# 13_TYPEC0_PROG.net
KiCad netlist of a schematic drawn in Altium Designer
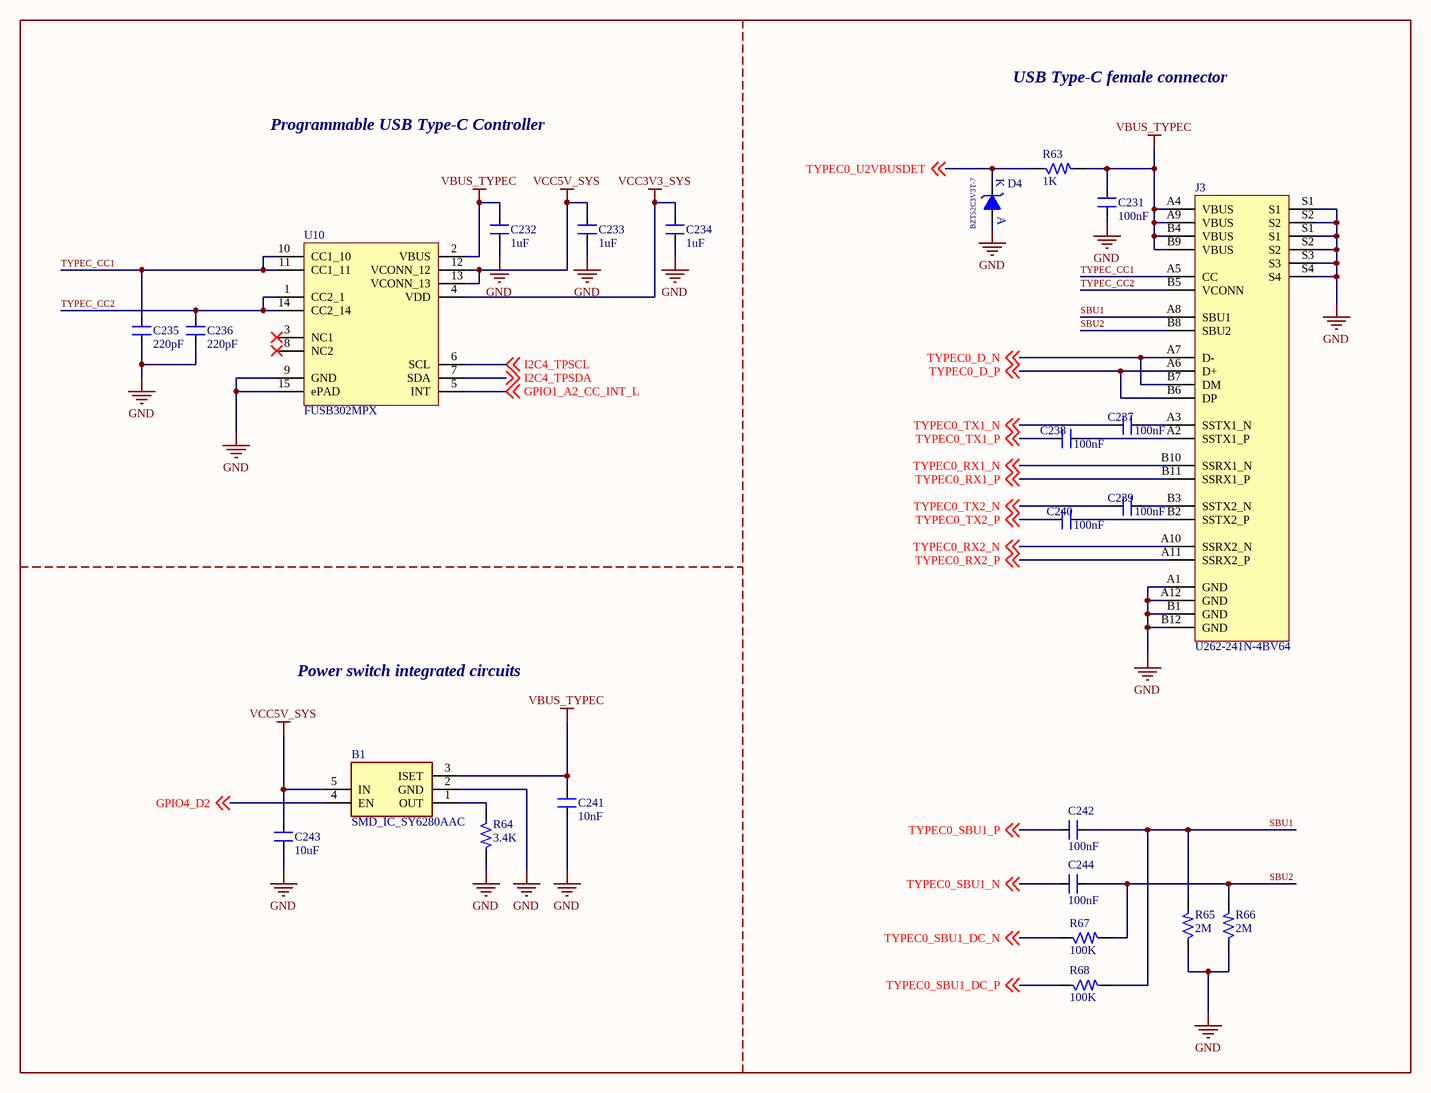
[diagram p0: [13] TYPEC0_PROG.SchDoc]

(export (version "E")
  (design (tool "Eeschema 10.0.6"))
  (components
    (comp (ref "B1")
      (value "SMD_IC_SY6280AAC")
      (footprint "SOT95P285X140-5N")
      (description "Power Switch ICs - Power Distribution")
      (fields
        (field (name "MOUSER PART NUMBER") "909-SMDICSY6280AAC")
        (field (name "MANUFACTURER_PART_NUMBER") "SMD IC SY6280AAC")
      )
      (libsource (lib "SMD_IC_SY6280AAC") (part "SMD_IC_SY6280AAC"))
    )
    (comp (ref "C231")
      (value "100nF")
      (footprint "CAP_0402")
      (description "0.1µF ±10% 25V Ceramic Capacitor X7R 0402 (1005 Metric)")
      (fields
        (field (name "MANUFACTURER") "Walsin Technology Corporation")
        (field (name "MANUFACTURER PART NUMBER") "0402B104K250CT")
      )
      (libsource (lib "EsteemPCB_SOM_Course_intlib") (part "CAP_100nF-25V-10%-0402"))
    )
    (comp (ref "C232")
      (value "1uF")
      (footprint "CAP_0402")
      (description "1µF ±10% 10V Ceramic Capacitor X6S 0402 (1005 Metric)")
      (fields
        (field (name "MANUFACTURER") "Murata Electronics")
        (field (name "MANUFACTURER PART NUMBER") "GRT155C81A105KE01D")
      )
      (libsource (lib "EsteemPCB_SOM_Course_intlib") (part "CAP_1uF-10V-10%-0402"))
    )
    (comp (ref "C233")
      (value "1uF")
      (footprint "CAP_0402")
      (description "1µF ±10% 10V Ceramic Capacitor X6S 0402 (1005 Metric)")
      (fields
        (field (name "MANUFACTURER") "Murata Electronics")
        (field (name "MANUFACTURER PART NUMBER") "GRT155C81A105KE01D")
      )
      (libsource (lib "EsteemPCB_SOM_Course_intlib") (part "CAP_1uF-10V-10%-0402"))
    )
    (comp (ref "C234")
      (value "1uF")
      (footprint "CAP_0402")
      (description "1µF ±10% 10V Ceramic Capacitor X6S 0402 (1005 Metric)")
      (fields
        (field (name "MANUFACTURER") "Murata Electronics")
        (field (name "MANUFACTURER PART NUMBER") "GRT155C81A105KE01D")
      )
      (libsource (lib "EsteemPCB_SOM_Course_intlib") (part "CAP_1uF-10V-10%-0402"))
    )
    (comp (ref "C235")
      (value "220pF")
      (footprint "CAP_0402")
      (description "220pF ±10% 10V Ceramic Capacitor X7R 0402 (1005 Metric)")
      (fields
        (field (name "MANUFACTURER") "KEMET")
        (field (name "MANUFACTURER PART NUMBER") "C0402C221K8RAC7867")
      )
      (libsource (lib "EsteemPCB_SOM_Course_intlib") (part "CAP_220pF-10V-10%-0402"))
    )
    (comp (ref "C236")
      (value "220pF")
      (footprint "CAP_0402")
      (description "220pF ±10% 10V Ceramic Capacitor X7R 0402 (1005 Metric)")
      (fields
        (field (name "MANUFACTURER") "KEMET")
        (field (name "MANUFACTURER PART NUMBER") "C0402C221K8RAC7867")
      )
      (libsource (lib "EsteemPCB_SOM_Course_intlib") (part "CAP_220pF-10V-10%-0402"))
    )
    (comp (ref "C237")
      (value "100nF")
      (footprint "CAP_0201")
      (description "0.1µF ±10% 25V Ceramic Capacitor X5R 0201 (0603 Metric)")
      (fields
        (field (name "MANUFACTURER") "TDK Corporation")
        (field (name "MANUFACTURER PART NUMBER") "C0603X5R1E104K030BB")
      )
      (libsource (lib "EsteemPCB_SOM_Course_intlib") (part "CAP_100nF-25V-10%-0201"))
    )
    (comp (ref "C238")
      (value "100nF")
      (footprint "CAP_0201")
      (description "0.1µF ±10% 25V Ceramic Capacitor X5R 0201 (0603 Metric)")
      (fields
        (field (name "MANUFACTURER") "TDK Corporation")
        (field (name "MANUFACTURER PART NUMBER") "C0603X5R1E104K030BB")
      )
      (libsource (lib "EsteemPCB_SOM_Course_intlib") (part "CAP_100nF-25V-10%-0201"))
    )
    (comp (ref "C239")
      (value "100nF")
      (footprint "CAP_0201")
      (description "0.1µF ±10% 25V Ceramic Capacitor X5R 0201 (0603 Metric)")
      (fields
        (field (name "MANUFACTURER") "TDK Corporation")
        (field (name "MANUFACTURER PART NUMBER") "C0603X5R1E104K030BB")
      )
      (libsource (lib "EsteemPCB_SOM_Course_intlib") (part "CAP_100nF-25V-10%-0201"))
    )
    (comp (ref "C240")
      (value "100nF")
      (footprint "CAP_0201")
      (description "0.1µF ±10% 25V Ceramic Capacitor X5R 0201 (0603 Metric)")
      (fields
        (field (name "MANUFACTURER") "TDK Corporation")
        (field (name "MANUFACTURER PART NUMBER") "C0603X5R1E104K030BB")
      )
      (libsource (lib "EsteemPCB_SOM_Course_intlib") (part "CAP_100nF-25V-10%-0201"))
    )
    (comp (ref "C241")
      (value "10nF")
      (footprint "CAP_0402")
      (description "10000pF ±10% 10V Ceramic Capacitor X7R 0402 (1005 Metric)")
      (fields
        (field (name "MANUFACTURER") "AVX Corporation")
        (field (name "MANUFACTURER PART NUMBER") "0402ZC103KAT2A")
      )
      (libsource (lib "EsteemPCB_SOM_Course_intlib") (part "CAP_10nF-10V-10%-0402"))
    )
    (comp (ref "C242")
      (value "100nF")
      (footprint "CAP_0201")
      (description "0.1µF ±10% 25V Ceramic Capacitor X5R 0201 (0603 Metric)")
      (fields
        (field (name "MANUFACTURER") "TDK Corporation")
        (field (name "MANUFACTURER PART NUMBER") "C0603X5R1E104K030BB")
      )
      (libsource (lib "EsteemPCB_SOM_Course_intlib") (part "CAP_100nF-25V-10%-0201"))
    )
    (comp (ref "C243")
      (value "10uF")
      (footprint "CAP_0402")
      (description "10µF ±20% 10V Ceramic Capacitor X5R 0402 (1005 Metric)")
      (fields
        (field (name "MANUFACTURER PART NUMBER") "CL05A106MP5NUNC")
        (field (name "MANUFACTURER") "Samsung Electro-Mechanics")
      )
      (libsource (lib "EsteemPCB_SOM_Course_intlib") (part "CAP_10uF-10V-20%-0402"))
    )
    (comp (ref "C244")
      (value "100nF")
      (footprint "CAP_0201")
      (description "0.1µF ±10% 25V Ceramic Capacitor X5R 0201 (0603 Metric)")
      (fields
        (field (name "MANUFACTURER") "TDK Corporation")
        (field (name "MANUFACTURER PART NUMBER") "C0603X5R1E104K030BB")
      )
      (libsource (lib "EsteemPCB_SOM_Course_intlib") (part "CAP_100nF-25V-10%-0201"))
    )
    (comp (ref "D4")
      (value "BZT52C3V3T-7")
      (footprint "DIO_SOD523")
      (description "Zener Diode 3.3V 300mW ±6% Surface Mount SOD-523")
      (fields (field (name "MANUFACTURER") "Diodes Incorporated"))
      (libsource (lib "EsteemPCB_SOM_Course_intlib") (part "DIO-Z_3.3V-300mW-SOD-523"))
    )
    (comp (ref "J3")
      (value "U262-241N-4BV64")
      (footprint "CON24_19.64_U262-241N-4BV64_TH_RA")
      (description "USB - Type C Female 24 SMD USB Connectors RoHS")
      (fields (field (name "MANUFACTURER") "XKB Connectivity"))
      (libsource (lib "EsteemPCB_SOM_Course_intlib") (part "CON-TYPEC_U262-241N-4BV64-SMD"))
    )
    (comp (ref "R63")
      (value "1K")
      (footprint "RES_0402")
      (description "1 kOhms ±1% 0.1W, 1/10W Chip Resistor 0402 (1005 Metric) Anti-Sulfur Thin Film")
      (fields
        (field (name "MANUFACTURER") "Vishay Beyschlag/Draloric/BC Components")
        (field (name "MANUFACTURER PART NUMBER") "MCS04020C1001FE000")
      )
      (libsource (lib "EsteemPCB_SOM_Course_intlib") (part "RES_1K-0.1W-1%-0402"))
    )
    (comp (ref "R64")
      (value "3.4K")
      (footprint "RES_0402")
      (description "3.4 kOhms ±1% 0.1W, 1/10W Chip Resistor 0402 (1005 Metric) Automotive AEC-Q200 Thick Film")
      (fields
        (field (name "MANUFACTURER") "Panasonic Electronic Components")
        (field (name "MANUFACTURER PART NUMBER") "ERJ-2RKF3401X")
      )
      (libsource (lib "EsteemPCB_SOM_Course_intlib") (part "RES_3.4K-0.1W-1%-0402"))
    )
    (comp (ref "R65")
      (value "2M")
      (footprint "RES_0201")
      (description "2 MOhms ±1% 0.05W, 1/20W Chip Resistor 0201 (0603 Metric) Thick Film")
      (fields
        (field (name "MANUFACTURER") "Yageo")
        (field (name "MANUFACTURER PART NUMBER") "RC0201FR-072ML")
      )
      (libsource (lib "EsteemPCB_SOM_Course_intlib") (part "RES_2M-0.05W-1%-0201"))
    )
    (comp (ref "R66")
      (value "2M")
      (footprint "RES_0201")
      (description "2 MOhms ±1% 0.05W, 1/20W Chip Resistor 0201 (0603 Metric) Thick Film")
      (fields
        (field (name "MANUFACTURER") "Yageo")
        (field (name "MANUFACTURER PART NUMBER") "RC0201FR-072ML")
      )
      (libsource (lib "EsteemPCB_SOM_Course_intlib") (part "RES_2M-0.05W-1%-0201"))
    )
    (comp (ref "R67")
      (value "100K")
      (footprint "RES_0201")
      (description "100 kOhms ±1% 0.05W, 1/20W Chip Resistor 0201 (0603 Metric) Automotive AEC-Q200 Thick Film")
      (fields
        (field (name "MANUFACTURER") "Panasonic Electronic Components")
        (field (name "MANUFACTURER PART NUMBER") "ERJ-1GNF1003C")
      )
      (libsource (lib "EsteemPCB_SOM_Course_intlib") (part "RES_100K-0.05W-1%-0201"))
    )
    (comp (ref "R68")
      (value "100K")
      (footprint "RES_0201")
      (description "100 kOhms ±1% 0.05W, 1/20W Chip Resistor 0201 (0603 Metric) Automotive AEC-Q200 Thick Film")
      (fields
        (field (name "MANUFACTURER") "Panasonic Electronic Components")
        (field (name "MANUFACTURER PART NUMBER") "ERJ-1GNF1003C")
      )
      (libsource (lib "EsteemPCB_SOM_Course_intlib") (part "RES_100K-0.05W-1%-0201"))
    )
    (comp (ref "U10")
      (value "FUSB302MPX")
      (footprint "MLP-14_98.4X98.4_SMD")
      (description "USB Controller USB 3.1 USB Interface 14-MLP (2.5x2.5)")
      (fields (field (name "MANUFACTURER") "ON Semiconductor"))
      (libsource (lib "EsteemPCB_SOM_Course_intlib") (part "IC_FUSB302MPX"))
    )
  )
  (nets
    (net (code "1") (name "/SBU1") (class "Default")
      (node (ref "C242") (pin "2") (pinfunction "2_2") (pintype "passive"))
      (node (ref "J3") (pin "A8") (pinfunction "SBU1_A8") (pintype "passive"))
      (node (ref "R65") (pin "2") (pinfunction "2_2") (pintype "passive"))
      (node (ref "R68") (pin "2") (pinfunction "2_2") (pintype "passive"))
    )
    (net (code "2") (name "/SBU2") (class "Default")
      (node (ref "C244") (pin "2") (pinfunction "2_2") (pintype "passive"))
      (node (ref "J3") (pin "B8") (pinfunction "SBU2_B8") (pintype "passive"))
      (node (ref "R66") (pin "2") (pinfunction "2_2") (pintype "passive"))
      (node (ref "R67") (pin "2") (pinfunction "2_2") (pintype "passive"))
    )
    (net (code "3") (name "/TYPEC_CC1") (class "Default")
      (node (ref "C235") (pin "2") (pinfunction "2_2") (pintype "passive"))
      (node (ref "J3") (pin "A5") (pinfunction "CC_A5") (pintype "passive"))
      (node (ref "U10") (pin "10") (pinfunction "CC1_10_10") (pintype "passive"))
      (node (ref "U10") (pin "11") (pinfunction "CC1_11_11") (pintype "passive"))
    )
    (net (code "4") (name "/TYPEC_CC2") (class "Default")
      (node (ref "C236") (pin "2") (pinfunction "2_2") (pintype "passive"))
      (node (ref "J3") (pin "B5") (pinfunction "VCONN_B5") (pintype "passive"))
      (node (ref "U10") (pin "1") (pinfunction "CC2_1_1") (pintype "passive"))
      (node (ref "U10") (pin "14") (pinfunction "CC2_14_14") (pintype "passive"))
    )
    (net (code "5") (name "GND") (class "Default")
      (node (ref "B1") (pin "2") (pinfunction "GND_2") (pintype "passive"))
      (node (ref "C231") (pin "1") (pinfunction "1_1") (pintype "passive"))
      (node (ref "C232") (pin "1") (pinfunction "1_1") (pintype "passive"))
      (node (ref "C233") (pin "2") (pinfunction "2_2") (pintype "passive"))
      (node (ref "C234") (pin "1") (pinfunction "1_1") (pintype "passive"))
      (node (ref "C235") (pin "1") (pinfunction "1_1") (pintype "passive"))
      (node (ref "C236") (pin "1") (pinfunction "1_1") (pintype "passive"))
      (node (ref "C241") (pin "1") (pinfunction "1_1") (pintype "passive"))
      (node (ref "C243") (pin "1") (pinfunction "1_1") (pintype "passive"))
      (node (ref "D4") (pin "A") (pinfunction "A_A") (pintype "passive"))
      (node (ref "J3") (pin "A1") (pinfunction "GND_A1") (pintype "passive"))
      (node (ref "J3") (pin "A12") (pinfunction "GND_A12") (pintype "passive"))
      (node (ref "J3") (pin "B1") (pinfunction "GND_B1") (pintype "passive"))
      (node (ref "J3") (pin "B12") (pinfunction "GND_B12") (pintype "passive"))
      (node (ref "J3") (pin "S1") (pinfunction "S1_S1") (pintype "passive"))
      (node (ref "J3") (pin "S2") (pinfunction "S2_S2") (pintype "passive"))
      (node (ref "J3") (pin "S3") (pinfunction "S3_S3") (pintype "passive"))
      (node (ref "J3") (pin "S4") (pinfunction "S4_S4") (pintype "passive"))
      (node (ref "R64") (pin "2") (pinfunction "2_2") (pintype "passive"))
      (node (ref "R65") (pin "1") (pinfunction "1_1") (pintype "passive"))
      (node (ref "R66") (pin "1") (pinfunction "1_1") (pintype "passive"))
      (node (ref "U10") (pin "15") (pinfunction "ePAD_15") (pintype "passive"))
      (node (ref "U10") (pin "9") (pinfunction "GND_9") (pintype "passive"))
    )
    (net (code "6") (name "GPIO1_A2_CC_INT_L") (class "Default")
      (node (ref "U10") (pin "5") (pinfunction "INT_5") (pintype "passive"))
    )
    (net (code "7") (name "GPIO4_D2") (class "Default")
      (node (ref "B1") (pin "4") (pinfunction "EN_4") (pintype "passive"))
    )
    (net (code "8") (name "I2C4_TPSCL") (class "Default")
      (node (ref "U10") (pin "6") (pinfunction "SCL_6") (pintype "passive"))
    )
    (net (code "9") (name "I2C4_TPSDA") (class "Default")
      (node (ref "U10") (pin "7") (pinfunction "SDA_7") (pintype "passive"))
    )
    (net (code "10") (name "Net-(B1-OUT)") (class "Default")
      (node (ref "B1") (pin "1") (pinfunction "OUT_1") (pintype "passive"))
      (node (ref "R64") (pin "1") (pinfunction "1_1") (pintype "passive"))
    )
    (net (code "11") (name "Net-(J3-SSTX1_N)") (class "Default")
      (node (ref "C237") (pin "2") (pinfunction "2_2") (pintype "passive"))
      (node (ref "J3") (pin "A3") (pinfunction "SSTX1_N_A3") (pintype "passive"))
    )
    (net (code "12") (name "Net-(J3-SSTX1_P)") (class "Default")
      (node (ref "C238") (pin "2") (pinfunction "2_2") (pintype "passive"))
      (node (ref "J3") (pin "A2") (pinfunction "SSTX1_P_A2") (pintype "passive"))
    )
    (net (code "13") (name "Net-(J3-SSTX2_N)") (class "Default")
      (node (ref "C239") (pin "2") (pinfunction "2_2") (pintype "passive"))
      (node (ref "J3") (pin "B3") (pinfunction "SSTX2_N_B3") (pintype "passive"))
    )
    (net (code "14") (name "Net-(J3-SSTX2_P)") (class "Default")
      (node (ref "C240") (pin "2") (pinfunction "2_2") (pintype "passive"))
      (node (ref "J3") (pin "B2") (pinfunction "SSTX2_P_B2") (pintype "passive"))
    )
    (net (code "15") (name "TYPEC0_D_N") (class "Default")
      (node (ref "J3") (pin "A7") (pinfunction "D-_A7") (pintype "passive"))
      (node (ref "J3") (pin "B7") (pinfunction "DM_B7") (pintype "passive"))
    )
    (net (code "16") (name "TYPEC0_D_P") (class "Default")
      (node (ref "J3") (pin "A6") (pinfunction "D+_A6") (pintype "passive"))
      (node (ref "J3") (pin "B6") (pinfunction "DP_B6") (pintype "passive"))
    )
    (net (code "17") (name "TYPEC0_RX1_N") (class "Default")
      (node (ref "J3") (pin "B10") (pinfunction "SSRX1_N_B10") (pintype "passive"))
    )
    (net (code "18") (name "TYPEC0_RX1_P") (class "Default")
      (node (ref "J3") (pin "B11") (pinfunction "SSRX1_P_B11") (pintype "passive"))
    )
    (net (code "19") (name "TYPEC0_RX2_N") (class "Default")
      (node (ref "J3") (pin "A10") (pinfunction "SSRX2_N_A10") (pintype "passive"))
    )
    (net (code "20") (name "TYPEC0_RX2_P") (class "Default")
      (node (ref "J3") (pin "A11") (pinfunction "SSRX2_P_A11") (pintype "passive"))
    )
    (net (code "21") (name "TYPEC0_SBU1_DC_N") (class "Default")
      (node (ref "R67") (pin "1") (pinfunction "1_1") (pintype "passive"))
    )
    (net (code "22") (name "TYPEC0_SBU1_DC_P") (class "Default")
      (node (ref "R68") (pin "1") (pinfunction "1_1") (pintype "passive"))
    )
    (net (code "23") (name "TYPEC0_SBU1_N") (class "Default")
      (node (ref "C244") (pin "1") (pinfunction "1_1") (pintype "passive"))
    )
    (net (code "24") (name "TYPEC0_SBU1_P") (class "Default")
      (node (ref "C242") (pin "1") (pinfunction "1_1") (pintype "passive"))
    )
    (net (code "25") (name "TYPEC0_TX1_N") (class "Default")
      (node (ref "C237") (pin "1") (pinfunction "1_1") (pintype "passive"))
    )
    (net (code "26") (name "TYPEC0_TX1_P") (class "Default")
      (node (ref "C238") (pin "1") (pinfunction "1_1") (pintype "passive"))
    )
    (net (code "27") (name "TYPEC0_TX2_N") (class "Default")
      (node (ref "C239") (pin "1") (pinfunction "1_1") (pintype "passive"))
    )
    (net (code "28") (name "TYPEC0_TX2_P") (class "Default")
      (node (ref "C240") (pin "1") (pinfunction "1_1") (pintype "passive"))
    )
    (net (code "29") (name "TYPEC0_U2VBUSDET") (class "Default")
      (node (ref "D4") (pin "K") (pinfunction "K_K") (pintype "passive"))
      (node (ref "R63") (pin "1") (pinfunction "1_1") (pintype "passive"))
    )
    (net (code "30") (name "VBUS_TYPEC") (class "Default")
      (node (ref "B1") (pin "3") (pinfunction "ISET_3") (pintype "passive"))
      (node (ref "C231") (pin "2") (pinfunction "2_2") (pintype "passive"))
      (node (ref "C232") (pin "2") (pinfunction "2_2") (pintype "passive"))
      (node (ref "C241") (pin "2") (pinfunction "2_2") (pintype "passive"))
      (node (ref "J3") (pin "A4") (pinfunction "VBUS_A4") (pintype "passive"))
      (node (ref "J3") (pin "A9") (pinfunction "VBUS_A9") (pintype "passive"))
      (node (ref "J3") (pin "B4") (pinfunction "VBUS_B4") (pintype "passive"))
      (node (ref "J3") (pin "B9") (pinfunction "VBUS_B9") (pintype "passive"))
      (node (ref "R63") (pin "2") (pinfunction "2_2") (pintype "passive"))
      (node (ref "U10") (pin "2") (pinfunction "VBUS_2") (pintype "passive"))
    )
    (net (code "31") (name "VCC3V3_SYS") (class "Default")
      (node (ref "C234") (pin "2") (pinfunction "2_2") (pintype "passive"))
      (node (ref "U10") (pin "4") (pinfunction "VDD_4") (pintype "passive"))
    )
    (net (code "32") (name "VCC5V_SYS") (class "Default")
      (node (ref "B1") (pin "5") (pinfunction "IN_5") (pintype "passive"))
      (node (ref "C233") (pin "1") (pinfunction "1_1") (pintype "passive"))
      (node (ref "C243") (pin "2") (pinfunction "2_2") (pintype "passive"))
      (node (ref "U10") (pin "12") (pinfunction "VCONN_12_12") (pintype "passive"))
      (node (ref "U10") (pin "13") (pinfunction "VCONN_13_13") (pintype "passive"))
    )
    (net (code "33") (name "unconnected-(U10-NC1-Pad3)") (class "Default")
      (node (ref "U10") (pin "3") (pinfunction "NC1_3") (pintype "passive+no_connect"))
    )
    (net (code "34") (name "unconnected-(U10-NC2-Pad8)") (class "Default")
      (node (ref "U10") (pin "8") (pinfunction "NC2_8") (pintype "passive+no_connect"))
    )
  )
)
